# FLYBACK.net
KiCad netlist of a schematic drawn in Altium Designer
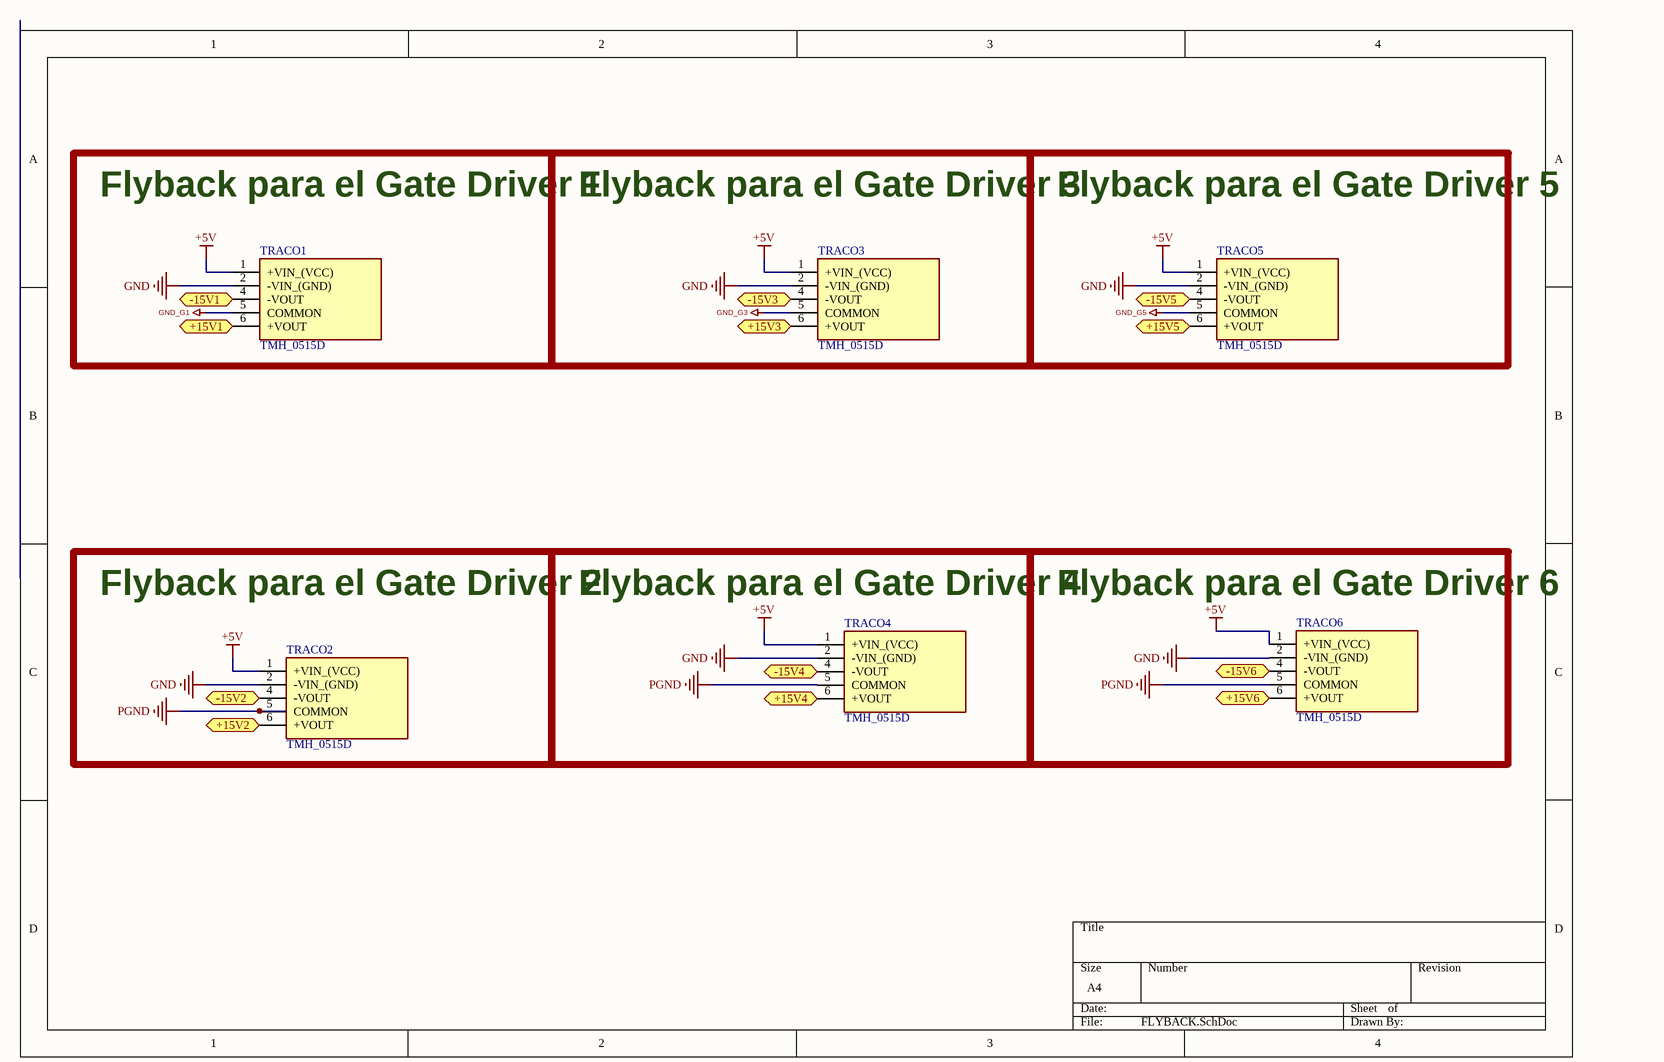
[diagram p0: FLYBACK.SchDoc]

(export (version "E")
  (design (tool "Eeschema 10.0.6"))
  (components
    (comp (ref "TRACO1")
      (value "TMH_0515D")
      (footprint "jasiel:TMH0515D")
      (description "DC/DC CONVERTER")
      (fields
        (field (name "MOUSER2 PART NUMBER") "495-TMH-0515D")
        (field (name "MANUFACTURER_PART_NUMBER") "TMH 0515D")
      )
      (libsource (lib "sch jasiel") (part "TMH_0515D"))
    )
    (comp (ref "TRACO2")
      (value "TMH_0515D")
      (footprint "jasiel:TMH0515D")
      (description "DC/DC CONVERTER")
      (fields
        (field (name "MOUSER2 PART NUMBER") "495-TMH-0515D")
        (field (name "MANUFACTURER_PART_NUMBER") "TMH 0515D")
      )
      (libsource (lib "sch jasiel") (part "TMH_0515D"))
    )
    (comp (ref "TRACO3")
      (value "TMH_0515D")
      (footprint "jasiel:TMH0515D")
      (description "DC/DC CONVERTER")
      (fields
        (field (name "MOUSER2 PART NUMBER") "495-TMH-0515D")
        (field (name "MANUFACTURER_PART_NUMBER") "TMH 0515D")
      )
      (libsource (lib "sch jasiel") (part "TMH_0515D"))
    )
    (comp (ref "TRACO4")
      (value "TMH_0515D")
      (footprint "jasiel:TMH0515D")
      (description "DC/DC CONVERTER")
      (fields
        (field (name "MOUSER2 PART NUMBER") "495-TMH-0515D")
        (field (name "MANUFACTURER_PART_NUMBER") "TMH 0515D")
      )
      (libsource (lib "sch jasiel") (part "TMH_0515D"))
    )
    (comp (ref "TRACO5")
      (value "TMH_0515D")
      (footprint "jasiel:TMH0515D")
      (description "DC/DC CONVERTER")
      (fields
        (field (name "MOUSER2 PART NUMBER") "495-TMH-0515D")
        (field (name "MANUFACTURER_PART_NUMBER") "TMH 0515D")
      )
      (libsource (lib "sch jasiel") (part "TMH_0515D"))
    )
    (comp (ref "TRACO6")
      (value "TMH_0515D")
      (footprint "jasiel:TMH0515D")
      (description "DC/DC CONVERTER")
      (fields
        (field (name "MOUSER2 PART NUMBER") "495-TMH-0515D")
        (field (name "MANUFACTURER_PART_NUMBER") "TMH 0515D")
      )
      (libsource (lib "sch jasiel") (part "TMH_0515D"))
    )
  )
  (nets
    (net (code "1") (name "+5V") (class "Default")
      (node (ref "TRACO1") (pin "1") (pinfunction "+VIN_(VCC)_1") (pintype "passive"))
      (node (ref "TRACO2") (pin "1") (pinfunction "+VIN_(VCC)_1") (pintype "passive"))
      (node (ref "TRACO3") (pin "1") (pinfunction "+VIN_(VCC)_1") (pintype "passive"))
      (node (ref "TRACO4") (pin "1") (pinfunction "+VIN_(VCC)_1") (pintype "passive"))
      (node (ref "TRACO5") (pin "1") (pinfunction "+VIN_(VCC)_1") (pintype "passive"))
      (node (ref "TRACO6") (pin "1") (pinfunction "+VIN_(VCC)_1") (pintype "passive"))
    )
    (net (code "2") (name "/+15V1") (class "Default")
      (node (ref "TRACO1") (pin "6") (pinfunction "+VOUT_6") (pintype "passive"))
    )
    (net (code "3") (name "/+15V2") (class "Default")
      (node (ref "TRACO2") (pin "6") (pinfunction "+VOUT_6") (pintype "passive"))
    )
    (net (code "4") (name "/+15V3") (class "Default")
      (node (ref "TRACO3") (pin "6") (pinfunction "+VOUT_6") (pintype "passive"))
    )
    (net (code "5") (name "/+15V4") (class "Default")
      (node (ref "TRACO4") (pin "6") (pinfunction "+VOUT_6") (pintype "passive"))
    )
    (net (code "6") (name "/+15V5") (class "Default")
      (node (ref "TRACO5") (pin "6") (pinfunction "+VOUT_6") (pintype "passive"))
    )
    (net (code "7") (name "/+15V6") (class "Default")
      (node (ref "TRACO6") (pin "6") (pinfunction "+VOUT_6") (pintype "passive"))
    )
    (net (code "8") (name "/-15V1") (class "Default")
      (node (ref "TRACO1") (pin "4") (pinfunction "-VOUT_4") (pintype "passive"))
    )
    (net (code "9") (name "/-15V2") (class "Default")
      (node (ref "TRACO2") (pin "4") (pinfunction "-VOUT_4") (pintype "passive"))
    )
    (net (code "10") (name "/-15V3") (class "Default")
      (node (ref "TRACO3") (pin "4") (pinfunction "-VOUT_4") (pintype "passive"))
    )
    (net (code "11") (name "/-15V4") (class "Default")
      (node (ref "TRACO4") (pin "4") (pinfunction "-VOUT_4") (pintype "passive"))
    )
    (net (code "12") (name "/-15V5") (class "Default")
      (node (ref "TRACO5") (pin "4") (pinfunction "-VOUT_4") (pintype "passive"))
    )
    (net (code "13") (name "/-15V6") (class "Default")
      (node (ref "TRACO6") (pin "4") (pinfunction "-VOUT_4") (pintype "passive"))
    )
    (net (code "14") (name "GND") (class "Default")
      (node (ref "TRACO1") (pin "2") (pinfunction "-VIN_(GND)_2") (pintype "passive"))
      (node (ref "TRACO2") (pin "2") (pinfunction "-VIN_(GND)_2") (pintype "passive"))
      (node (ref "TRACO3") (pin "2") (pinfunction "-VIN_(GND)_2") (pintype "passive"))
      (node (ref "TRACO4") (pin "2") (pinfunction "-VIN_(GND)_2") (pintype "passive"))
      (node (ref "TRACO5") (pin "2") (pinfunction "-VIN_(GND)_2") (pintype "passive"))
      (node (ref "TRACO6") (pin "2") (pinfunction "-VIN_(GND)_2") (pintype "passive"))
    )
    (net (code "15") (name "GND_G1") (class "Default")
      (node (ref "TRACO1") (pin "5") (pinfunction "COMMON_5") (pintype "passive"))
    )
    (net (code "16") (name "GND_G3") (class "Default")
      (node (ref "TRACO3") (pin "5") (pinfunction "COMMON_5") (pintype "passive"))
    )
    (net (code "17") (name "GND_G5") (class "Default")
      (node (ref "TRACO5") (pin "5") (pinfunction "COMMON_5") (pintype "passive"))
    )
    (net (code "18") (name "PGND") (class "Default")
      (node (ref "TRACO2") (pin "5") (pinfunction "COMMON_5") (pintype "passive"))
      (node (ref "TRACO4") (pin "5") (pinfunction "COMMON_5") (pintype "passive"))
      (node (ref "TRACO6") (pin "5") (pinfunction "COMMON_5") (pintype "passive"))
    )
  )
)
